# IMU.net
KiCad netlist of a schematic drawn in EAGLE
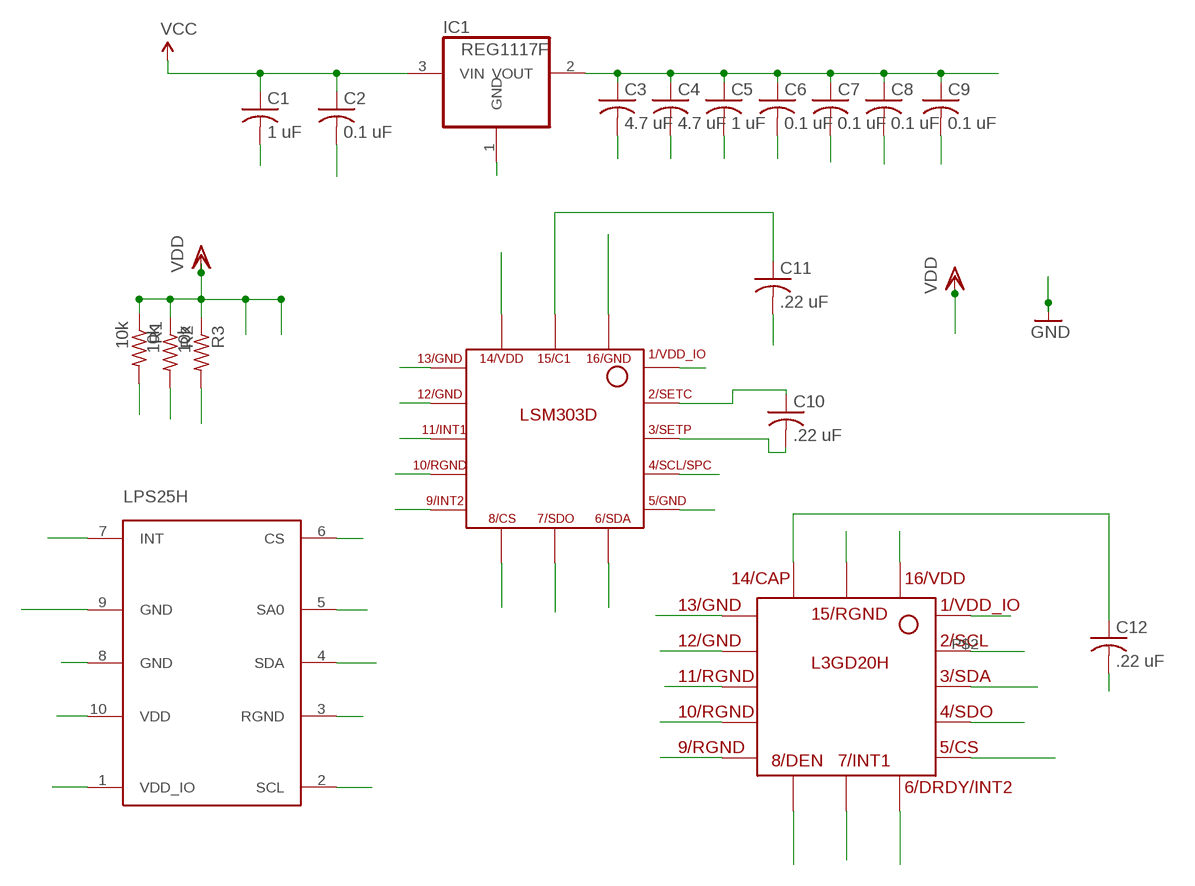
[diagram p0: schematic, sheet 1]

(export (version "E")
  (design (tool "Eeschema 10.0.6"))
  (components
    (comp (ref "C1")
      (value "1 uF")
      (footprint "eagle-import:C0805")
      (libsource (lib "eagle-import") (part "C-USC0805"))
    )
    (comp (ref "C2")
      (value "0.1 uF")
      (footprint "eagle-import:C0805")
      (libsource (lib "eagle-import") (part "C-USC0805"))
    )
    (comp (ref "C3")
      (value "4.7 uF")
      (footprint "eagle-import:C0805")
      (libsource (lib "eagle-import") (part "C-USC0805"))
    )
    (comp (ref "C4")
      (value "4.7 uF")
      (footprint "eagle-import:C0805")
      (libsource (lib "eagle-import") (part "C-USC0805"))
    )
    (comp (ref "C5")
      (value "1 uF")
      (footprint "eagle-import:C0805")
      (libsource (lib "eagle-import") (part "C-USC0805"))
    )
    (comp (ref "C6")
      (value "0.1 uF")
      (footprint "eagle-import:C0805")
      (libsource (lib "eagle-import") (part "C-USC0805"))
    )
    (comp (ref "C7")
      (value "0.1 uF")
      (footprint "eagle-import:C0805")
      (libsource (lib "eagle-import") (part "C-USC0805"))
    )
    (comp (ref "C8")
      (value "0.1 uF")
      (footprint "eagle-import:C0805")
      (libsource (lib "eagle-import") (part "C-USC0805"))
    )
    (comp (ref "C9")
      (value "0.1 uF")
      (footprint "eagle-import:C0805")
      (libsource (lib "eagle-import") (part "C-USC0805"))
    )
    (comp (ref "C10")
      (value ".22 uF")
      (footprint "eagle-import:C0805")
      (libsource (lib "eagle-import") (part "C-USC0805"))
    )
    (comp (ref "C11")
      (value ".22 uF")
      (footprint "eagle-import:C0805")
      (libsource (lib "eagle-import") (part "C-USC0805"))
    )
    (comp (ref "C12")
      (value ".22 uF")
      (footprint "eagle-import:C0805")
      (libsource (lib "eagle-import") (part "C-USC0805"))
    )
    (comp (ref "IC1")
      (value "REG1117F")
      (footprint "eagle-import:DD-3")
      (fields (field (name "MF") "TEXAS INSTRUMENTS") (field (name "MPN") "REG1117FAKTTT"))
      (libsource (lib "eagle-import") (part "REG1117F"))
    )
    (comp (ref "LPS25H")
      (value "LPS25H")
      (footprint "eagle-import:LPS25H")
      (libsource (lib "eagle-import") (part "LPS25H"))
    )
    (comp (ref "R1")
      (value "10k")
      (footprint "eagle-import:R0805")
      (libsource (lib "eagle-import") (part "R-US_R0805"))
    )
    (comp (ref "R2")
      (value "10k")
      (footprint "eagle-import:R0805")
      (libsource (lib "eagle-import") (part "R-US_R0805"))
    )
    (comp (ref "R3")
      (value "10k")
      (footprint "eagle-import:R0805")
      (libsource (lib "eagle-import") (part "R-US_R0805"))
    )
    (comp (ref "U$1")
      (value "LSM303D")
      (footprint "eagle-import:LGA-16")
      (libsource (lib "eagle-import") (part "LSM303D"))
    )
    (comp (ref "U$2")
      (value "L3GD20H")
      (footprint "eagle-import:LGA-16")
      (libsource (lib "eagle-import") (part "L3GD20H"))
    )
  )
  (nets
    (net (code "1") (name "/SCL") (class "Default")
      (node (ref "LPS25H") (pin "2") (pinfunction "SCL_2") (pintype "bidirectional"))
      (node (ref "R2") (pin "2") (pinfunction "2_2") (pintype "passive"))
      (node (ref "U$1") (pin "P$4") (pinfunction "4/SCL/SPC_P$4") (pintype "bidirectional"))
      (node (ref "U$2") (pin "P$2") (pinfunction "2/SCL_P$2") (pintype "bidirectional"))
    )
    (net (code "2") (name "/SDA") (class "Default")
      (node (ref "LPS25H") (pin "4") (pinfunction "SDA_4") (pintype "bidirectional"))
      (node (ref "R1") (pin "2") (pinfunction "2_2") (pintype "passive"))
      (node (ref "U$1") (pin "P$6") (pinfunction "6/SDA/SDI/SDO_P$6") (pintype "bidirectional"))
      (node (ref "U$2") (pin "P$3") (pinfunction "3/SDA_P$3") (pintype "bidirectional"))
    )
    (net (code "3") (name "/SDO") (class "Default")
      (node (ref "LPS25H") (pin "5") (pinfunction "SA0_5") (pintype "bidirectional"))
      (node (ref "R3") (pin "2") (pinfunction "2_2") (pintype "passive"))
      (node (ref "U$1") (pin "P$7") (pinfunction "7/SDO/SA0_P$7") (pintype "bidirectional"))
      (node (ref "U$2") (pin "P$4") (pinfunction "4/SDO_P$4") (pintype "bidirectional"))
    )
    (net (code "4") (name "GND") (class "Default")
      (node (ref "C1") (pin "2") (pinfunction "2_2") (pintype "passive"))
      (node (ref "C11") (pin "2") (pinfunction "2_2") (pintype "passive"))
      (node (ref "C12") (pin "2") (pinfunction "2_2") (pintype "passive"))
      (node (ref "C2") (pin "2") (pinfunction "2_2") (pintype "passive"))
      (node (ref "C3") (pin "2") (pinfunction "2_2") (pintype "passive"))
      (node (ref "C4") (pin "2") (pinfunction "2_2") (pintype "passive"))
      (node (ref "C5") (pin "2") (pinfunction "2_2") (pintype "passive"))
      (node (ref "C6") (pin "2") (pinfunction "2_2") (pintype "passive"))
      (node (ref "C7") (pin "2") (pinfunction "2_2") (pintype "passive"))
      (node (ref "C8") (pin "2") (pinfunction "2_2") (pintype "passive"))
      (node (ref "C9") (pin "2") (pinfunction "2_2") (pintype "passive"))
      (node (ref "IC1") (pin "1") (pinfunction "GND_1") (pintype "power_in"))
      (node (ref "LPS25H") (pin "8") (pinfunction "GND_8") (pintype "power_in"))
      (node (ref "LPS25H") (pin "9") (pinfunction "GND_9") (pintype "power_in"))
      (node (ref "U$1") (pin "P$10") (pinfunction "10/RGND_P$10") (pintype "bidirectional"))
      (node (ref "U$1") (pin "P$12") (pinfunction "12/GND_P$12") (pintype "bidirectional"))
      (node (ref "U$1") (pin "P$13") (pinfunction "13/GND_P$13") (pintype "bidirectional"))
      (node (ref "U$1") (pin "P$16") (pinfunction "16/GND_P$16") (pintype "bidirectional"))
      (node (ref "U$2") (pin "P$10") (pinfunction "10/RGND_P$10") (pintype "bidirectional"))
      (node (ref "U$2") (pin "P$11") (pinfunction "11/RGND_P$11") (pintype "bidirectional"))
      (node (ref "U$2") (pin "P$12") (pinfunction "12/GND_P$12") (pintype "bidirectional"))
      (node (ref "U$2") (pin "P$13") (pinfunction "13/GND_P$13") (pintype "bidirectional"))
      (node (ref "U$2") (pin "P$15") (pinfunction "15/RGND_P$15") (pintype "bidirectional"))
      (node (ref "U$2") (pin "P$9") (pinfunction "9/RGND_P$9") (pintype "bidirectional"))
    )
    (net (code "5") (name "Net-(U$1-2{slash}SETC)") (class "Default")
      (node (ref "C10") (pin "1") (pinfunction "1_1") (pintype "passive"))
      (node (ref "U$1") (pin "P$2") (pinfunction "2/SETC_P$2") (pintype "bidirectional"))
    )
    (net (code "6") (name "Net-(U$1-3{slash}SETP)") (class "Default")
      (node (ref "C10") (pin "2") (pinfunction "2_2") (pintype "passive"))
      (node (ref "U$1") (pin "P$3") (pinfunction "3/SETP_P$3") (pintype "bidirectional"))
    )
    (net (code "7") (name "Net-(U$1-15{slash}C1)") (class "Default")
      (node (ref "C11") (pin "1") (pinfunction "1_1") (pintype "passive"))
      (node (ref "U$1") (pin "P$15") (pinfunction "15/C1_P$15") (pintype "bidirectional"))
    )
    (net (code "8") (name "Net-(U$2-14{slash}CAP)") (class "Default")
      (node (ref "C12") (pin "1") (pinfunction "1_1") (pintype "passive"))
      (node (ref "U$2") (pin "P$14") (pinfunction "14/CAP_P$14") (pintype "bidirectional"))
    )
    (net (code "9") (name "VCC") (class "Default")
      (node (ref "C1") (pin "1") (pinfunction "1_1") (pintype "passive"))
      (node (ref "C2") (pin "1") (pinfunction "1_1") (pintype "passive"))
      (node (ref "IC1") (pin "3") (pinfunction "VIN_3") (pintype "input"))
    )
    (net (code "10") (name "VDD") (class "Default")
      (node (ref "C3") (pin "1") (pinfunction "1_1") (pintype "passive"))
      (node (ref "C4") (pin "1") (pinfunction "1_1") (pintype "passive"))
      (node (ref "C5") (pin "1") (pinfunction "1_1") (pintype "passive"))
      (node (ref "C6") (pin "1") (pinfunction "1_1") (pintype "passive"))
      (node (ref "C7") (pin "1") (pinfunction "1_1") (pintype "passive"))
      (node (ref "C8") (pin "1") (pinfunction "1_1") (pintype "passive"))
      (node (ref "C9") (pin "1") (pinfunction "1_1") (pintype "passive"))
      (node (ref "IC1") (pin "2") (pinfunction "VOUT_2") (pintype "output"))
      (node (ref "LPS25H") (pin "1") (pinfunction "VDD_IO_1") (pintype "power_in"))
      (node (ref "LPS25H") (pin "10") (pinfunction "VDD_10") (pintype "power_in"))
      (node (ref "LPS25H") (pin "6") (pinfunction "CS_6") (pintype "bidirectional"))
      (node (ref "R1") (pin "1") (pinfunction "1_1") (pintype "passive"))
      (node (ref "R2") (pin "1") (pinfunction "1_1") (pintype "passive"))
      (node (ref "R3") (pin "1") (pinfunction "1_1") (pintype "passive"))
      (node (ref "U$1") (pin "P$1") (pinfunction "1/VDD_IO_P$1") (pintype "bidirectional"))
      (node (ref "U$1") (pin "P$14") (pinfunction "14/VDD_P$14") (pintype "bidirectional"))
      (node (ref "U$1") (pin "P$8") (pinfunction "8/CS_P$8") (pintype "bidirectional"))
      (node (ref "U$2") (pin "P$1") (pinfunction "1/VDD_IO_P$1") (pintype "bidirectional"))
      (node (ref "U$2") (pin "P$16") (pinfunction "16/VDD_P$16") (pintype "bidirectional"))
      (node (ref "U$2") (pin "P$5") (pinfunction "5/CS_P$5") (pintype "bidirectional"))
    )
    (net (code "11") (name "unconnected-(LPS25H-INT-Pad7)") (class "Default")
      (node (ref "LPS25H") (pin "7") (pinfunction "INT_7") (pintype "bidirectional"))
    )
    (net (code "12") (name "unconnected-(LPS25H-RGND-Pad3)") (class "Default")
      (node (ref "LPS25H") (pin "3") (pinfunction "RGND_3") (pintype "bidirectional"))
    )
    (net (code "13") (name "unconnected-(U$1-5{slash}GND-PadP$5)") (class "Default")
      (node (ref "U$1") (pin "P$5") (pinfunction "5/GND_P$5") (pintype "bidirectional"))
    )
    (net (code "14") (name "unconnected-(U$1-9{slash}INT2-PadP$9)") (class "Default")
      (node (ref "U$1") (pin "P$9") (pinfunction "9/INT2_P$9") (pintype "bidirectional"))
    )
    (net (code "15") (name "unconnected-(U$1-11{slash}INT1-PadP$11)") (class "Default")
      (node (ref "U$1") (pin "P$11") (pinfunction "11/INT1_P$11") (pintype "bidirectional"))
    )
    (net (code "16") (name "unconnected-(U$2-6{slash}DRDY{slash}INT2-PadP$6)") (class "Default")
      (node (ref "U$2") (pin "P$6") (pinfunction "6/DRDY/INT2_P$6") (pintype "bidirectional"))
    )
    (net (code "17") (name "unconnected-(U$2-7{slash}INT1-PadP$7)") (class "Default")
      (node (ref "U$2") (pin "P$7") (pinfunction "7/INT1_P$7") (pintype "bidirectional"))
    )
    (net (code "18") (name "unconnected-(U$2-8{slash}DEN-PadP$8)") (class "Default")
      (node (ref "U$2") (pin "P$8") (pinfunction "8/DEN_P$8") (pintype "bidirectional"))
    )
  )
)
